# ArduSensor-Switch.net
KiCad netlist of a schematic drawn in EAGLE
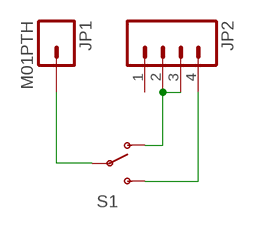
[diagram p0: schematic, sheet 1]

(export (version "E")
  (design (tool "Eeschema 10.0.6"))
  (components
    (comp (ref "JP1")
      (value "M01PTH")
      (footprint "eagle-import:1X01")
      (libsource (lib "eagle-import") (part "M01PTH"))
    )
    (comp (ref "JP2")
      (value "M04PTH")
      (footprint "eagle-import:1X04")
      (libsource (lib "eagle-import") (part "M04PTH"))
    )
    (comp (ref "S1")
      (value "SWITCH-SPDTPTH")
      (footprint "eagle-import:SWITCH-SPDT")
      (libsource (lib "eagle-import") (part "SWITCH-SPDTPTH"))
    )
  )
  (nets
    (net (code "1") (name "Net-(S1-O)") (class "Default")
      (node (ref "JP2") (pin "2") (pinfunction "2_2") (pintype "passive"))
      (node (ref "JP2") (pin "3") (pinfunction "3_3") (pintype "passive"))
      (node (ref "S1") (pin "1") (pinfunction "O_1") (pintype "passive"))
    )
    (net (code "2") (name "Net-(S1-P)") (class "Default")
      (node (ref "JP1") (pin "1") (pinfunction "1_1") (pintype "passive"))
      (node (ref "S1") (pin "2") (pinfunction "P_2") (pintype "passive"))
    )
    (net (code "3") (name "Net-(S1-S)") (class "Default")
      (node (ref "JP2") (pin "4") (pinfunction "4_4") (pintype "passive"))
      (node (ref "S1") (pin "3") (pinfunction "S_3") (pintype "passive"))
    )
    (net (code "4") (name "unconnected-(JP2-Pad1)") (class "Default")
      (node (ref "JP2") (pin "1") (pinfunction "1_1") (pintype "passive"))
    )
  )
)
